# main.net
KiCad netlist of a schematic drawn in EAGLE
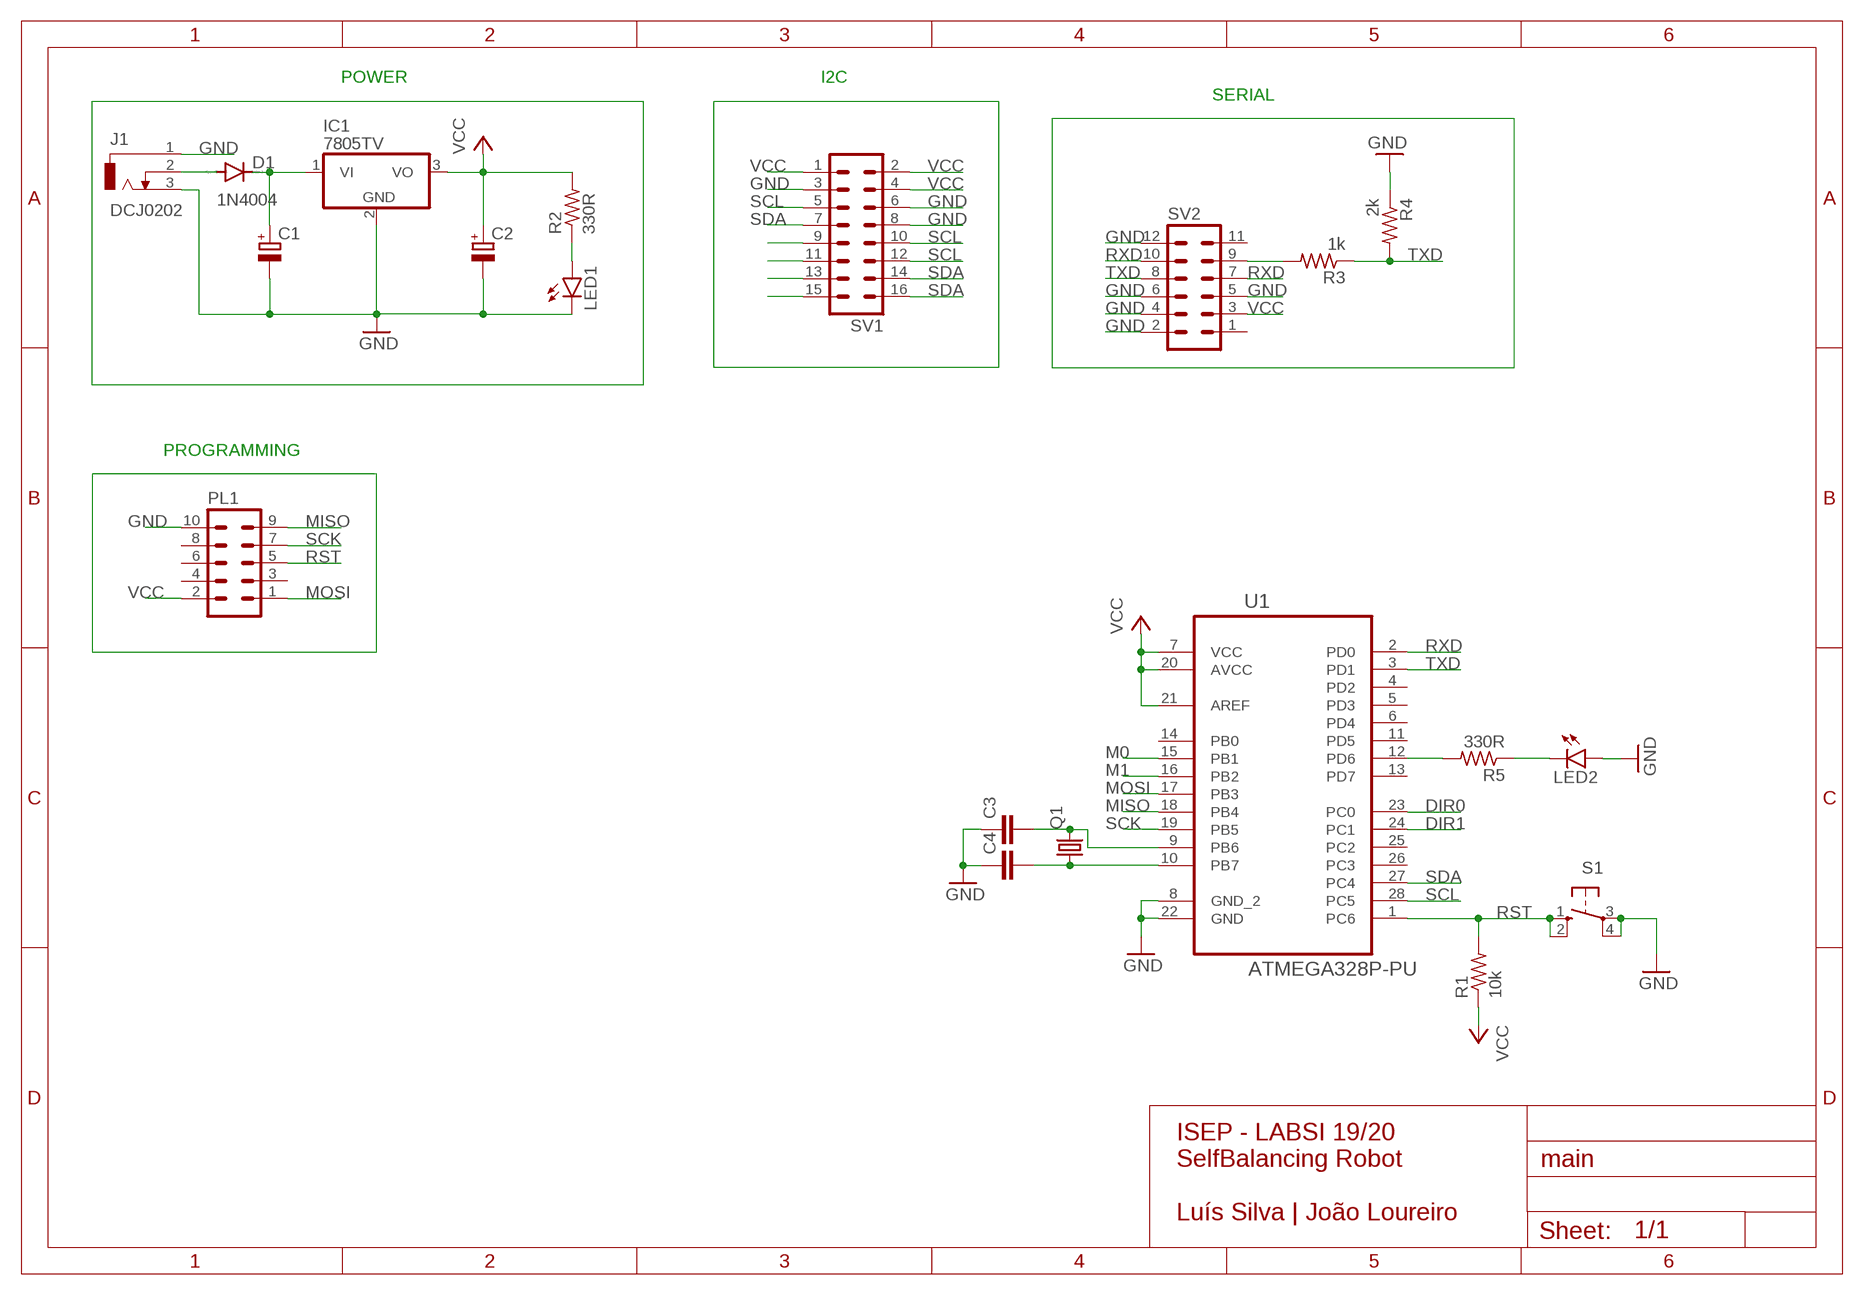
[diagram p0: schematic, sheet 1]

(export (version "E")
  (design (tool "Eeschema 10.0.6"))
  (components
    (comp (ref "C1")
      (value "CPOL-EUB45181A")
      (footprint "eagle-import:B45181A")
      (libsource (lib "eagle-import") (part "CPOL-EUB45181A"))
    )
    (comp (ref "C2")
      (value "CPOL-EUB45181A")
      (footprint "eagle-import:B45181A")
      (libsource (lib "eagle-import") (part "CPOL-EUB45181A"))
    )
    (comp (ref "C3")
      (value "C5/3")
      (footprint "eagle-import:C5B3")
      (libsource (lib "eagle-import") (part "C5/3"))
    )
    (comp (ref "C4")
      (value "C5/3")
      (footprint "eagle-import:C5B3")
      (libsource (lib "eagle-import") (part "C5/3"))
    )
    (comp (ref "D1")
      (value "1N4004")
      (footprint "eagle-import:DO41-10")
      (libsource (lib "eagle-import") (part "1N4004"))
    )
    (comp (ref "IC1")
      (value "7805TV")
      (footprint "eagle-import:TO220V")
      (libsource (lib "eagle-import") (part "78TV05"))
    )
    (comp (ref "J1")
      (value "DCJ0202")
      (footprint "eagle-import:DCJ0202")
      (libsource (lib "eagle-import") (part "DCJ0202"))
    )
    (comp (ref "LED1")
      (value "LED3MM")
      (footprint "eagle-import:LED3MM")
      (libsource (lib "eagle-import") (part "LED3MM"))
    )
    (comp (ref "LED2")
      (value "LED3MM")
      (footprint "eagle-import:LED3MM")
      (libsource (lib "eagle-import") (part "LED3MM"))
    )
    (comp (ref "PL1")
      (value "10H")
      (footprint "eagle-import:10H")
      (libsource (lib "eagle-import") (part "10H"))
    )
    (comp (ref "Q1")
      (value "CRYSTALHC49S")
      (footprint "eagle-import:HC49_S")
      (libsource (lib "eagle-import") (part "CRYSTALHC49S"))
    )
    (comp (ref "R1")
      (value "10k")
      (footprint "eagle-import:0207_10")
      (libsource (lib "eagle-import") (part "R-US_0207/10"))
    )
    (comp (ref "R2")
      (value "330R")
      (footprint "eagle-import:0207_10")
      (libsource (lib "eagle-import") (part "R-US_0207/10"))
    )
    (comp (ref "R3")
      (value "1k")
      (footprint "eagle-import:0207_10")
      (libsource (lib "eagle-import") (part "R-US_0207/10"))
    )
    (comp (ref "R4")
      (value "2k")
      (footprint "eagle-import:0207_10")
      (libsource (lib "eagle-import") (part "R-US_0207/10"))
    )
    (comp (ref "R5")
      (value "330R")
      (footprint "eagle-import:0207_10")
      (libsource (lib "eagle-import") (part "R-US_0207/10"))
    )
    (comp (ref "S1")
      (value "10-XX")
      (footprint "eagle-import:B3F-10XX")
      (fields (field (name "MPN") "B3F-1000"))
      (libsource (lib "eagle-import") (part "10-XX"))
    )
    (comp (ref "SV1")
      (value "MA08-2")
      (footprint "eagle-import:MA08-2")
      (libsource (lib "eagle-import") (part "MA08-2"))
    )
    (comp (ref "SV2")
      (value "MA06-2")
      (footprint "eagle-import:MA06-2")
      (libsource (lib "eagle-import") (part "MA06-2"))
    )
    (comp (ref "U1")
      (value "ATMEGA328P-PU")
      (footprint "eagle-import:DIP254P762X457-28")
      (fields (field (name "MF") "Generic"))
      (libsource (lib "eagle-import") (part "ATMEGA328P-PU"))
    )
  )
  (nets
    (net (code "1") (name "/DIR0") (class "Default")
      (node (ref "U1") (pin "23") (pinfunction "PC0_23") (pintype "bidirectional"))
    )
    (net (code "2") (name "/DIR1") (class "Default")
      (node (ref "U1") (pin "24") (pinfunction "PC1_24") (pintype "bidirectional"))
    )
    (net (code "3") (name "/M0") (class "Default")
      (node (ref "U1") (pin "15") (pinfunction "PB1_15") (pintype "bidirectional"))
    )
    (net (code "4") (name "/M1") (class "Default")
      (node (ref "U1") (pin "16") (pinfunction "PB2_16") (pintype "bidirectional"))
    )
    (net (code "5") (name "/MISO") (class "Default")
      (node (ref "PL1") (pin "9") (pinfunction "9_9") (pintype "passive"))
      (node (ref "U1") (pin "18") (pinfunction "PB4_18") (pintype "bidirectional"))
    )
    (net (code "6") (name "/MOSI") (class "Default")
      (node (ref "PL1") (pin "1") (pinfunction "1_1") (pintype "passive"))
      (node (ref "U1") (pin "17") (pinfunction "PB3_17") (pintype "bidirectional"))
    )
    (net (code "7") (name "/RST") (class "Default")
      (node (ref "PL1") (pin "5") (pinfunction "5_5") (pintype "passive"))
      (node (ref "R1") (pin "2") (pinfunction "2_2") (pintype "passive"))
      (node (ref "S1") (pin "1") (pinfunction "S_1") (pintype "passive"))
      (node (ref "S1") (pin "2") (pinfunction "S1_2") (pintype "passive"))
      (node (ref "U1") (pin "1") (pinfunction "PC6_1") (pintype "bidirectional"))
    )
    (net (code "8") (name "/RXD") (class "Default")
      (node (ref "SV2") (pin "10") (pinfunction "10_10") (pintype "passive"))
      (node (ref "SV2") (pin "7") (pinfunction "7_7") (pintype "passive"))
      (node (ref "U1") (pin "2") (pinfunction "PD0_2") (pintype "bidirectional"))
    )
    (net (code "9") (name "/SCK") (class "Default")
      (node (ref "PL1") (pin "7") (pinfunction "7_7") (pintype "passive"))
      (node (ref "U1") (pin "19") (pinfunction "PB5_19") (pintype "bidirectional"))
    )
    (net (code "10") (name "/SCL") (class "Default")
      (node (ref "SV1") (pin "10") (pinfunction "10_10") (pintype "passive"))
      (node (ref "SV1") (pin "12") (pinfunction "12_12") (pintype "passive"))
      (node (ref "SV1") (pin "5") (pinfunction "5_5") (pintype "passive"))
      (node (ref "U1") (pin "28") (pinfunction "PC5_28") (pintype "bidirectional"))
    )
    (net (code "11") (name "/SDA") (class "Default")
      (node (ref "SV1") (pin "14") (pinfunction "14_14") (pintype "passive"))
      (node (ref "SV1") (pin "16") (pinfunction "16_16") (pintype "passive"))
      (node (ref "SV1") (pin "7") (pinfunction "7_7") (pintype "passive"))
      (node (ref "U1") (pin "27") (pinfunction "PC4_27") (pintype "bidirectional"))
    )
    (net (code "12") (name "/TXD") (class "Default")
      (node (ref "R3") (pin "1") (pinfunction "1_1") (pintype "passive"))
      (node (ref "R4") (pin "2") (pinfunction "2_2") (pintype "passive"))
      (node (ref "SV2") (pin "8") (pinfunction "8_8") (pintype "passive"))
      (node (ref "U1") (pin "3") (pinfunction "PD1_3") (pintype "bidirectional"))
    )
    (net (code "13") (name "GND") (class "Default")
      (node (ref "C1") (pin "-") (pinfunction "-_-") (pintype "passive"))
      (node (ref "C2") (pin "-") (pinfunction "-_-") (pintype "passive"))
      (node (ref "C3") (pin "1") (pinfunction "1_1") (pintype "passive"))
      (node (ref "C4") (pin "1") (pinfunction "1_1") (pintype "passive"))
      (node (ref "IC1") (pin "2") (pinfunction "GND_2") (pintype "passive"))
      (node (ref "J1") (pin "1") (pinfunction "1_1") (pintype "passive"))
      (node (ref "J1") (pin "3") (pinfunction "3_3") (pintype "passive"))
      (node (ref "LED1") (pin "K") (pinfunction "C_K") (pintype "passive"))
      (node (ref "LED2") (pin "A") (pinfunction "A_A") (pintype "passive"))
      (node (ref "PL1") (pin "10") (pinfunction "10_10") (pintype "passive"))
      (node (ref "R4") (pin "1") (pinfunction "1_1") (pintype "passive"))
      (node (ref "S1") (pin "3") (pinfunction "P_3") (pintype "passive"))
      (node (ref "S1") (pin "4") (pinfunction "P1_4") (pintype "passive"))
      (node (ref "SV1") (pin "3") (pinfunction "3_3") (pintype "passive"))
      (node (ref "SV1") (pin "6") (pinfunction "6_6") (pintype "passive"))
      (node (ref "SV1") (pin "8") (pinfunction "8_8") (pintype "passive"))
      (node (ref "SV2") (pin "12") (pinfunction "12_12") (pintype "passive"))
      (node (ref "SV2") (pin "2") (pinfunction "2_2") (pintype "passive"))
      (node (ref "SV2") (pin "4") (pinfunction "4_4") (pintype "passive"))
      (node (ref "SV2") (pin "5") (pinfunction "5_5") (pintype "passive"))
      (node (ref "SV2") (pin "6") (pinfunction "6_6") (pintype "passive"))
      (node (ref "U1") (pin "22") (pinfunction "GND_22") (pintype "passive"))
      (node (ref "U1") (pin "8") (pinfunction "GND_2_8") (pintype "passive"))
    )
    (net (code "14") (name "Net-(D1-PadA)") (class "Default")
      (node (ref "D1") (pin "A") (pinfunction "A_A") (pintype "passive"))
      (node (ref "J1") (pin "2") (pinfunction "2_2") (pintype "passive"))
    )
    (net (code "15") (name "Net-(IC1-VI)") (class "Default")
      (node (ref "C1") (pin "+") (pinfunction "+_+") (pintype "passive"))
      (node (ref "D1") (pin "C") (pinfunction "C_C") (pintype "passive"))
      (node (ref "IC1") (pin "1") (pinfunction "VI_1") (pintype "input"))
    )
    (net (code "16") (name "Net-(LED1-PadA)") (class "Default")
      (node (ref "LED1") (pin "A") (pinfunction "A_A") (pintype "passive"))
      (node (ref "R2") (pin "1") (pinfunction "1_1") (pintype "passive"))
    )
    (net (code "17") (name "Net-(LED2-C)") (class "Default")
      (node (ref "LED2") (pin "K") (pinfunction "C_K") (pintype "passive"))
      (node (ref "R5") (pin "1") (pinfunction "1_1") (pintype "passive"))
    )
    (net (code "18") (name "Net-(R3-Pad2)") (class "Default")
      (node (ref "R3") (pin "2") (pinfunction "2_2") (pintype "passive"))
      (node (ref "SV2") (pin "9") (pinfunction "9_9") (pintype "passive"))
    )
    (net (code "19") (name "Net-(U1-PB6)") (class "Default")
      (node (ref "C3") (pin "2") (pinfunction "2_2") (pintype "passive"))
      (node (ref "Q1") (pin "2") (pinfunction "2_2") (pintype "passive"))
      (node (ref "U1") (pin "9") (pinfunction "PB6_9") (pintype "bidirectional"))
    )
    (net (code "20") (name "Net-(U1-PB7)") (class "Default")
      (node (ref "C4") (pin "2") (pinfunction "2_2") (pintype "passive"))
      (node (ref "Q1") (pin "1") (pinfunction "1_1") (pintype "passive"))
      (node (ref "U1") (pin "10") (pinfunction "PB7_10") (pintype "bidirectional"))
    )
    (net (code "21") (name "Net-(U1-PD6)") (class "Default")
      (node (ref "R5") (pin "2") (pinfunction "2_2") (pintype "passive"))
      (node (ref "U1") (pin "12") (pinfunction "PD6_12") (pintype "bidirectional"))
    )
    (net (code "22") (name "VCC") (class "Default")
      (node (ref "C2") (pin "+") (pinfunction "+_+") (pintype "passive"))
      (node (ref "IC1") (pin "3") (pinfunction "VO_3") (pintype "passive"))
      (node (ref "PL1") (pin "2") (pinfunction "2_2") (pintype "passive"))
      (node (ref "R1") (pin "1") (pinfunction "1_1") (pintype "passive"))
      (node (ref "R2") (pin "2") (pinfunction "2_2") (pintype "passive"))
      (node (ref "SV1") (pin "1") (pinfunction "1_1") (pintype "passive"))
      (node (ref "SV1") (pin "2") (pinfunction "2_2") (pintype "passive"))
      (node (ref "SV1") (pin "4") (pinfunction "4_4") (pintype "passive"))
      (node (ref "SV2") (pin "3") (pinfunction "3_3") (pintype "passive"))
      (node (ref "U1") (pin "20") (pinfunction "AVCC_20") (pintype "power_in"))
      (node (ref "U1") (pin "21") (pinfunction "AREF_21") (pintype "input"))
      (node (ref "U1") (pin "7") (pinfunction "VCC_7") (pintype "power_in"))
    )
    (net (code "23") (name "unconnected-(PL1-Pad3)") (class "Default")
      (node (ref "PL1") (pin "3") (pinfunction "3_3") (pintype "passive"))
    )
    (net (code "24") (name "unconnected-(PL1-Pad4)") (class "Default")
      (node (ref "PL1") (pin "4") (pinfunction "4_4") (pintype "passive"))
    )
    (net (code "25") (name "unconnected-(PL1-Pad6)") (class "Default")
      (node (ref "PL1") (pin "6") (pinfunction "6_6") (pintype "passive"))
    )
    (net (code "26") (name "unconnected-(PL1-Pad8)") (class "Default")
      (node (ref "PL1") (pin "8") (pinfunction "8_8") (pintype "passive"))
    )
    (net (code "27") (name "unconnected-(SV1-Pad9)") (class "Default")
      (node (ref "SV1") (pin "9") (pinfunction "9_9") (pintype "passive"))
    )
    (net (code "28") (name "unconnected-(SV1-Pad11)") (class "Default")
      (node (ref "SV1") (pin "11") (pinfunction "11_11") (pintype "passive"))
    )
    (net (code "29") (name "unconnected-(SV1-Pad13)") (class "Default")
      (node (ref "SV1") (pin "13") (pinfunction "13_13") (pintype "passive"))
    )
    (net (code "30") (name "unconnected-(SV1-Pad15)") (class "Default")
      (node (ref "SV1") (pin "15") (pinfunction "15_15") (pintype "passive"))
    )
    (net (code "31") (name "unconnected-(SV2-Pad1)") (class "Default")
      (node (ref "SV2") (pin "1") (pinfunction "1_1") (pintype "passive"))
    )
    (net (code "32") (name "unconnected-(SV2-Pad11)") (class "Default")
      (node (ref "SV2") (pin "11") (pinfunction "11_11") (pintype "passive"))
    )
    (net (code "33") (name "unconnected-(U1-PB0-Pad14)") (class "Default")
      (node (ref "U1") (pin "14") (pinfunction "PB0_14") (pintype "bidirectional"))
    )
    (net (code "34") (name "unconnected-(U1-PC2-Pad25)") (class "Default")
      (node (ref "U1") (pin "25") (pinfunction "PC2_25") (pintype "bidirectional"))
    )
    (net (code "35") (name "unconnected-(U1-PC3-Pad26)") (class "Default")
      (node (ref "U1") (pin "26") (pinfunction "PC3_26") (pintype "bidirectional"))
    )
    (net (code "36") (name "unconnected-(U1-PD2-Pad4)") (class "Default")
      (node (ref "U1") (pin "4") (pinfunction "PD2_4") (pintype "bidirectional"))
    )
    (net (code "37") (name "unconnected-(U1-PD3-Pad5)") (class "Default")
      (node (ref "U1") (pin "5") (pinfunction "PD3_5") (pintype "bidirectional"))
    )
    (net (code "38") (name "unconnected-(U1-PD4-Pad6)") (class "Default")
      (node (ref "U1") (pin "6") (pinfunction "PD4_6") (pintype "bidirectional"))
    )
    (net (code "39") (name "unconnected-(U1-PD5-Pad11)") (class "Default")
      (node (ref "U1") (pin "11") (pinfunction "PD5_11") (pintype "bidirectional"))
    )
    (net (code "40") (name "unconnected-(U1-PD7-Pad13)") (class "Default")
      (node (ref "U1") (pin "13") (pinfunction "PD7_13") (pintype "bidirectional"))
    )
  )
)
